# untitled.net
KiCad netlist of a schematic drawn in EAGLE
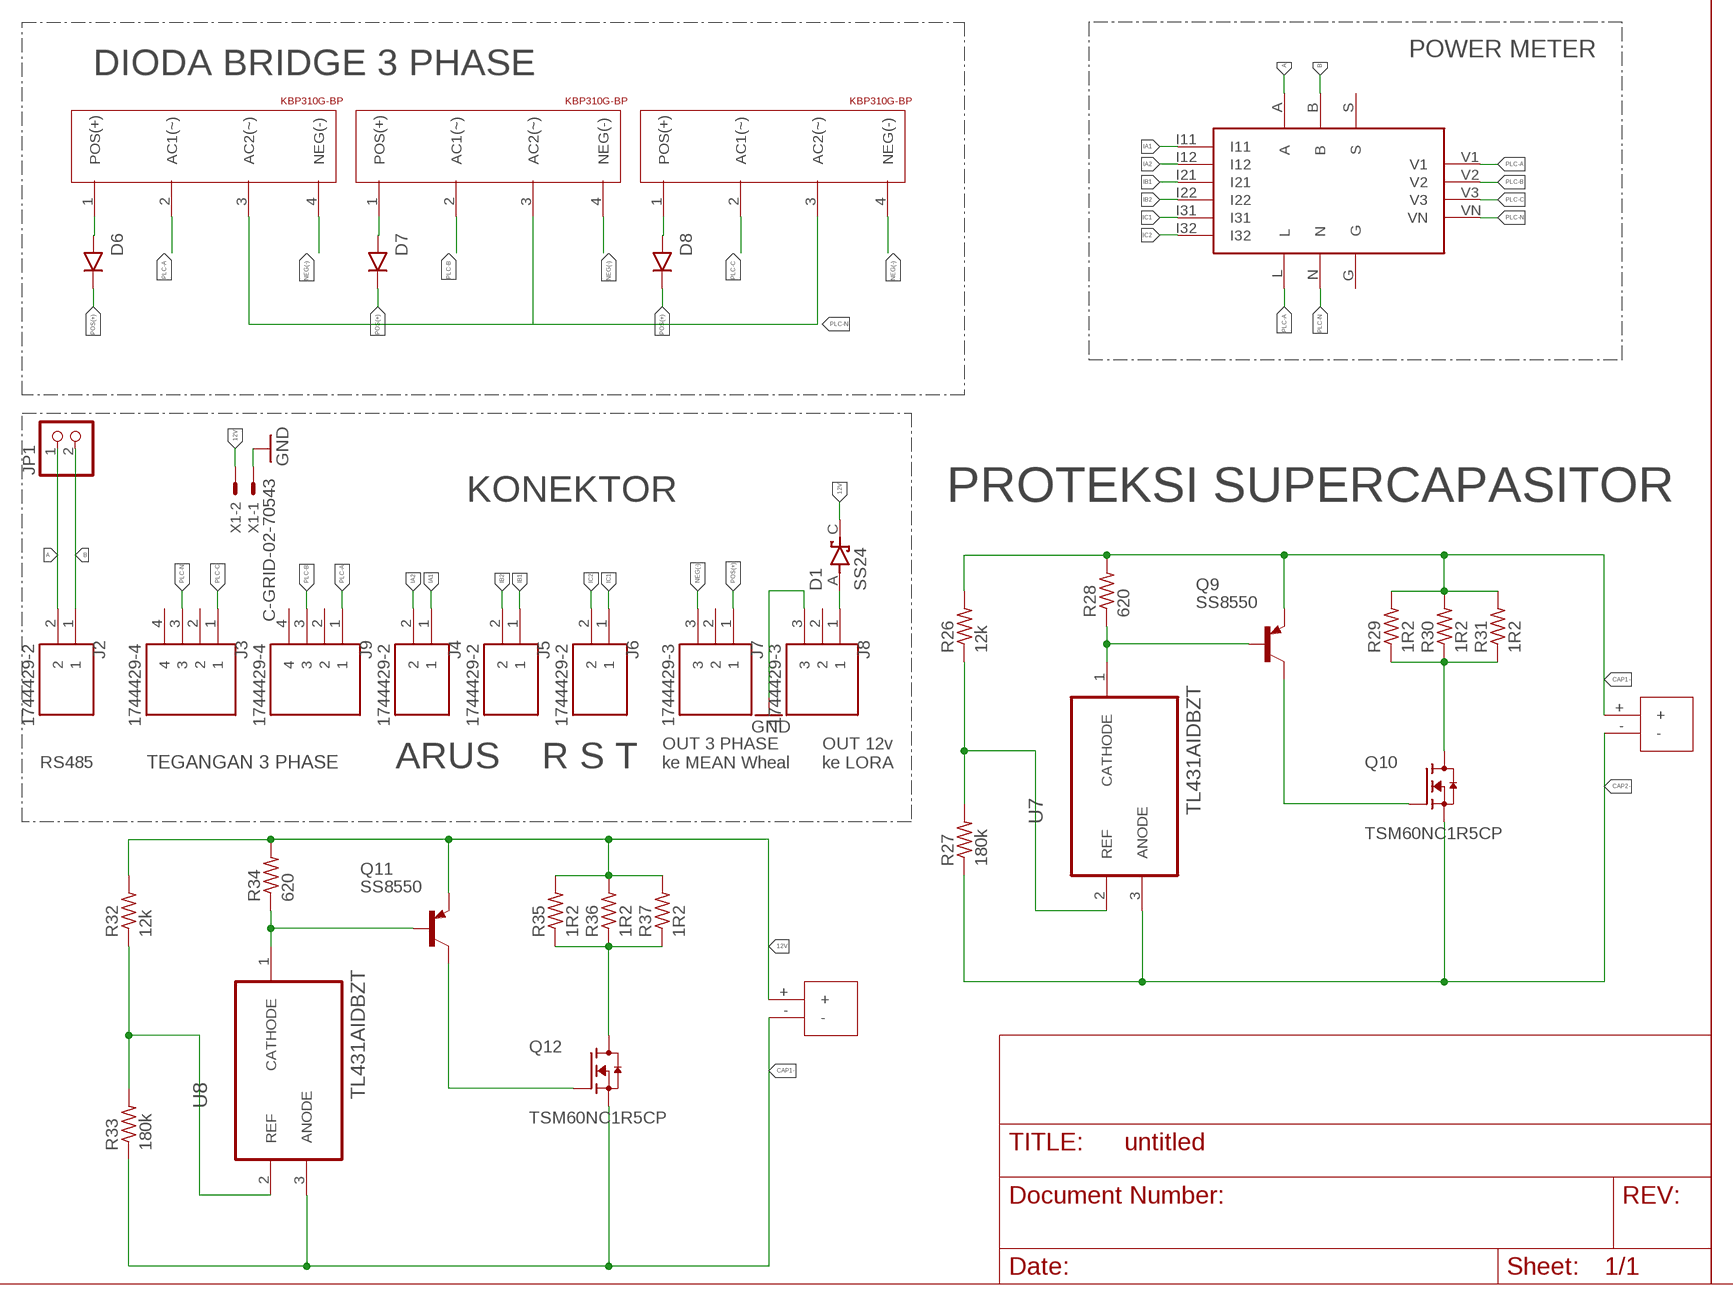
[diagram p0: schematic, sheet 1, part 1 of 2]
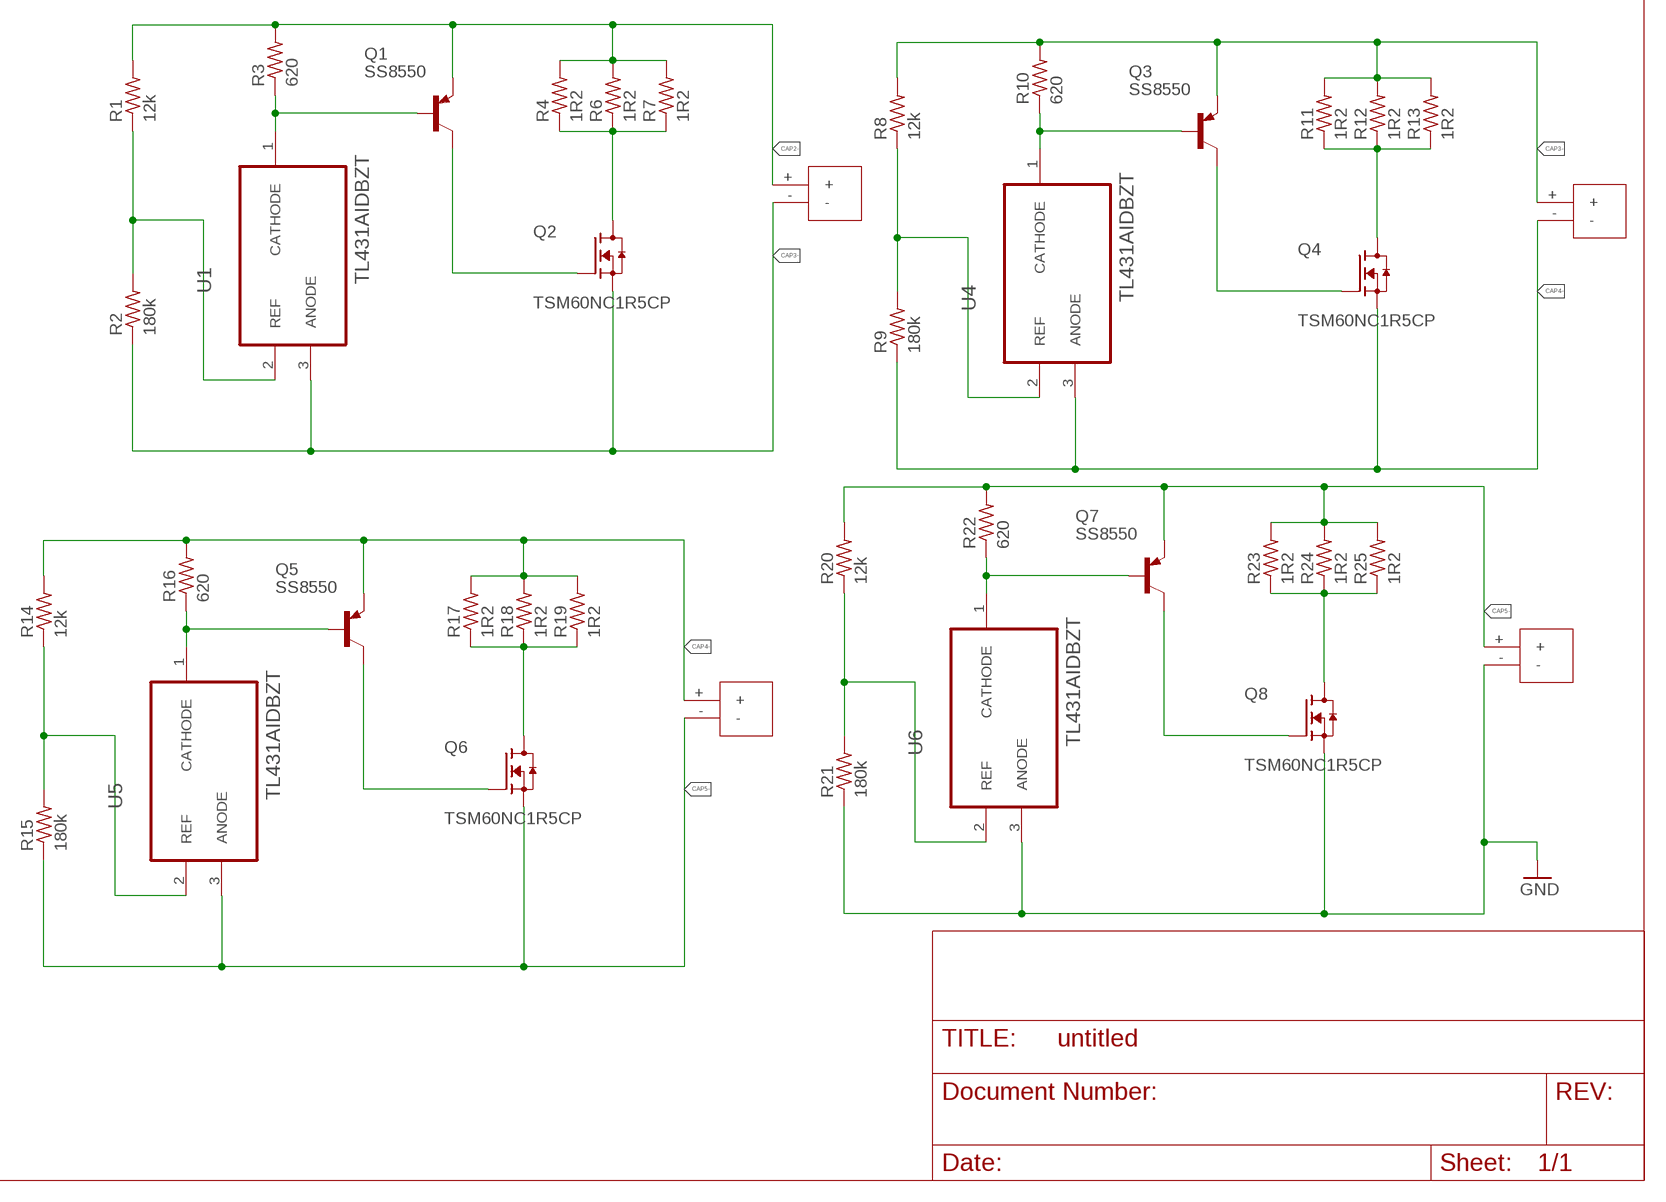
[diagram p1: schematic, sheet 1, part 2 of 2]

(export (version "E")
  (design (tool "Eeschema 10.0.6"))
  (components
    (comp (ref "D1")
      (value "SS24")
      (footprint "eagle-import:DIOM5336X265N")
      (fields (field (name "MF") "ON Semiconductor"))
      (libsource (lib "eagle-import") (part "SS24"))
    )
    (comp (ref "D6")
      (value "1N4001")
      (footprint "eagle-import:DO41-10")
      (fields (field (name "MF") "HVCA"))
      (libsource (lib "eagle-import") (part "1N4001"))
    )
    (comp (ref "D7")
      (value "1N4001")
      (footprint "eagle-import:DO41-10")
      (fields (field (name "MF") "HVCA"))
      (libsource (lib "eagle-import") (part "1N4001"))
    )
    (comp (ref "D8")
      (value "1N4001")
      (footprint "eagle-import:DO41-10")
      (fields (field (name "MF") "HVCA"))
      (libsource (lib "eagle-import") (part "1N4001"))
    )
    (comp (ref "J2")
      (value "1744429-2")
      (footprint "eagle-import:TE_1744429-2")
      (fields (field (name "MF") "TE Connectivity"))
      (libsource (lib "eagle-import") (part "1744429-2"))
    )
    (comp (ref "J3")
      (value "1744429-4")
      (footprint "eagle-import:TE_1744429-4")
      (fields (field (name "MF") "TE Connectivity"))
      (libsource (lib "eagle-import") (part "1744429-4"))
    )
    (comp (ref "J4")
      (value "1744429-2")
      (footprint "eagle-import:TE_1744429-2")
      (fields (field (name "MF") "TE Connectivity"))
      (libsource (lib "eagle-import") (part "1744429-2"))
    )
    (comp (ref "J5")
      (value "1744429-2")
      (footprint "eagle-import:TE_1744429-2")
      (fields (field (name "MF") "TE Connectivity"))
      (libsource (lib "eagle-import") (part "1744429-2"))
    )
    (comp (ref "J6")
      (value "1744429-2")
      (footprint "eagle-import:TE_1744429-2")
      (fields (field (name "MF") "TE Connectivity"))
      (libsource (lib "eagle-import") (part "1744429-2"))
    )
    (comp (ref "J7")
      (value "1744429-3")
      (footprint "eagle-import:TE_1744429-3")
      (fields (field (name "MANUFACTURER") "TE"))
      (libsource (lib "eagle-import") (part "1744429-3"))
    )
    (comp (ref "J8")
      (value "1744429-3")
      (footprint "eagle-import:TE_1744429-3")
      (fields (field (name "MANUFACTURER") "TE"))
      (libsource (lib "eagle-import") (part "1744429-3"))
    )
    (comp (ref "J9")
      (value "1744429-4")
      (footprint "eagle-import:TE_1744429-4")
      (fields (field (name "MF") "TE Connectivity"))
      (libsource (lib "eagle-import") (part "1744429-4"))
    )
    (comp (ref "JP1")
      (value "PINHD-1X2")
      (footprint "eagle-import:1X02")
      (libsource (lib "eagle-import") (part "PINHD-1X2"))
    )
    (comp (ref "POWERMETER1")
      (value "POWERMETER")
      (footprint "eagle-import:POWERMETER")
      (libsource (lib "eagle-import") (part "POWERMETER"))
    )
    (comp (ref "Q1")
      (value "SS8550")
      (footprint "eagle-import:SOT-23_BEC")
      (fields (field (name "MF") "ON Semiconductor / Fairchild"))
      (libsource (lib "eagle-import") (part "SS8550"))
    )
    (comp (ref "Q2")
      (value "TSM60NC1R5CP")
      (footprint "eagle-import:TRANS_TSM60NC1R5CP")
      (fields (field (name "MF") "Taiwan Semiconductor"))
      (libsource (lib "eagle-import") (part "TSM60NC1R5CP"))
    )
    (comp (ref "Q3")
      (value "SS8550")
      (footprint "eagle-import:SOT-23_BEC")
      (fields (field (name "MF") "ON Semiconductor / Fairchild"))
      (libsource (lib "eagle-import") (part "SS8550"))
    )
    (comp (ref "Q4")
      (value "TSM60NC1R5CP")
      (footprint "eagle-import:TRANS_TSM60NC1R5CP")
      (fields (field (name "MF") "Taiwan Semiconductor"))
      (libsource (lib "eagle-import") (part "TSM60NC1R5CP"))
    )
    (comp (ref "Q5")
      (value "SS8550")
      (footprint "eagle-import:SOT-23_BEC")
      (fields (field (name "MF") "ON Semiconductor / Fairchild"))
      (libsource (lib "eagle-import") (part "SS8550"))
    )
    (comp (ref "Q6")
      (value "TSM60NC1R5CP")
      (footprint "eagle-import:TRANS_TSM60NC1R5CP")
      (fields (field (name "MF") "Taiwan Semiconductor"))
      (libsource (lib "eagle-import") (part "TSM60NC1R5CP"))
    )
    (comp (ref "Q7")
      (value "SS8550")
      (footprint "eagle-import:SOT-23_BEC")
      (fields (field (name "MF") "ON Semiconductor / Fairchild"))
      (libsource (lib "eagle-import") (part "SS8550"))
    )
    (comp (ref "Q8")
      (value "TSM60NC1R5CP")
      (footprint "eagle-import:TRANS_TSM60NC1R5CP")
      (fields (field (name "MF") "Taiwan Semiconductor"))
      (libsource (lib "eagle-import") (part "TSM60NC1R5CP"))
    )
    (comp (ref "Q9")
      (value "SS8550")
      (footprint "eagle-import:SOT-23_BEC")
      (fields (field (name "MF") "ON Semiconductor / Fairchild"))
      (libsource (lib "eagle-import") (part "SS8550"))
    )
    (comp (ref "Q10")
      (value "TSM60NC1R5CP")
      (footprint "eagle-import:TRANS_TSM60NC1R5CP")
      (fields (field (name "MF") "Taiwan Semiconductor"))
      (libsource (lib "eagle-import") (part "TSM60NC1R5CP"))
    )
    (comp (ref "Q11")
      (value "SS8550")
      (footprint "eagle-import:SOT-23_BEC")
      (fields (field (name "MF") "ON Semiconductor / Fairchild"))
      (libsource (lib "eagle-import") (part "SS8550"))
    )
    (comp (ref "Q12")
      (value "TSM60NC1R5CP")
      (footprint "eagle-import:TRANS_TSM60NC1R5CP")
      (fields (field (name "MF") "Taiwan Semiconductor"))
      (libsource (lib "eagle-import") (part "TSM60NC1R5CP"))
    )
    (comp (ref "R1")
      (value "12k")
      (footprint "eagle-import:R0805")
      (libsource (lib "eagle-import") (part "R-US_R0805"))
    )
    (comp (ref "R2")
      (value "180k")
      (footprint "eagle-import:R0805")
      (libsource (lib "eagle-import") (part "R-US_R0805"))
    )
    (comp (ref "R3")
      (value "620")
      (footprint "eagle-import:R0805")
      (libsource (lib "eagle-import") (part "R-US_R0805"))
    )
    (comp (ref "R4")
      (value "1R2")
      (footprint "eagle-import:R2512")
      (libsource (lib "eagle-import") (part "rcl_334_R-US_R2512"))
    )
    (comp (ref "R6")
      (value "1R2")
      (footprint "eagle-import:R2512")
      (libsource (lib "eagle-import") (part "rcl_334_R-US_R2512"))
    )
    (comp (ref "R7")
      (value "1R2")
      (footprint "eagle-import:R2512")
      (libsource (lib "eagle-import") (part "rcl_334_R-US_R2512"))
    )
    (comp (ref "R8")
      (value "12k")
      (footprint "eagle-import:R0805")
      (libsource (lib "eagle-import") (part "R-US_R0805"))
    )
    (comp (ref "R9")
      (value "180k")
      (footprint "eagle-import:R0805")
      (libsource (lib "eagle-import") (part "R-US_R0805"))
    )
    (comp (ref "R10")
      (value "620")
      (footprint "eagle-import:R0805")
      (libsource (lib "eagle-import") (part "R-US_R0805"))
    )
    (comp (ref "R11")
      (value "1R2")
      (footprint "eagle-import:R2512")
      (libsource (lib "eagle-import") (part "rcl_334_R-US_R2512"))
    )
    (comp (ref "R12")
      (value "1R2")
      (footprint "eagle-import:R2512")
      (libsource (lib "eagle-import") (part "rcl_334_R-US_R2512"))
    )
    (comp (ref "R13")
      (value "1R2")
      (footprint "eagle-import:R2512")
      (libsource (lib "eagle-import") (part "rcl_334_R-US_R2512"))
    )
    (comp (ref "R14")
      (value "12k")
      (footprint "eagle-import:R0805")
      (libsource (lib "eagle-import") (part "R-US_R0805"))
    )
    (comp (ref "R15")
      (value "180k")
      (footprint "eagle-import:R0805")
      (libsource (lib "eagle-import") (part "R-US_R0805"))
    )
    (comp (ref "R16")
      (value "620")
      (footprint "eagle-import:R0805")
      (libsource (lib "eagle-import") (part "R-US_R0805"))
    )
    (comp (ref "R17")
      (value "1R2")
      (footprint "eagle-import:R2512")
      (libsource (lib "eagle-import") (part "rcl_334_R-US_R2512"))
    )
    (comp (ref "R18")
      (value "1R2")
      (footprint "eagle-import:R2512")
      (libsource (lib "eagle-import") (part "rcl_334_R-US_R2512"))
    )
    (comp (ref "R19")
      (value "1R2")
      (footprint "eagle-import:R2512")
      (libsource (lib "eagle-import") (part "rcl_334_R-US_R2512"))
    )
    (comp (ref "R20")
      (value "12k")
      (footprint "eagle-import:R0805")
      (libsource (lib "eagle-import") (part "R-US_R0805"))
    )
    (comp (ref "R21")
      (value "180k")
      (footprint "eagle-import:R0805")
      (libsource (lib "eagle-import") (part "R-US_R0805"))
    )
    (comp (ref "R22")
      (value "620")
      (footprint "eagle-import:R0805")
      (libsource (lib "eagle-import") (part "R-US_R0805"))
    )
    (comp (ref "R23")
      (value "1R2")
      (footprint "eagle-import:R2512")
      (libsource (lib "eagle-import") (part "rcl_334_R-US_R2512"))
    )
    (comp (ref "R24")
      (value "1R2")
      (footprint "eagle-import:R2512")
      (libsource (lib "eagle-import") (part "rcl_334_R-US_R2512"))
    )
    (comp (ref "R25")
      (value "1R2")
      (footprint "eagle-import:R2512")
      (libsource (lib "eagle-import") (part "rcl_334_R-US_R2512"))
    )
    (comp (ref "R26")
      (value "12k")
      (footprint "eagle-import:R0805")
      (libsource (lib "eagle-import") (part "R-US_R0805"))
    )
    (comp (ref "R27")
      (value "180k")
      (footprint "eagle-import:R0805")
      (libsource (lib "eagle-import") (part "R-US_R0805"))
    )
    (comp (ref "R28")
      (value "620")
      (footprint "eagle-import:R0805")
      (libsource (lib "eagle-import") (part "R-US_R0805"))
    )
    (comp (ref "R29")
      (value "1R2")
      (footprint "eagle-import:R2512")
      (libsource (lib "eagle-import") (part "rcl_334_R-US_R2512"))
    )
    (comp (ref "R30")
      (value "1R2")
      (footprint "eagle-import:R2512")
      (libsource (lib "eagle-import") (part "rcl_334_R-US_R2512"))
    )
    (comp (ref "R31")
      (value "1R2")
      (footprint "eagle-import:R2512")
      (libsource (lib "eagle-import") (part "rcl_334_R-US_R2512"))
    )
    (comp (ref "R32")
      (value "12k")
      (footprint "eagle-import:R0805")
      (libsource (lib "eagle-import") (part "R-US_R0805"))
    )
    (comp (ref "R33")
      (value "180k")
      (footprint "eagle-import:R0805")
      (libsource (lib "eagle-import") (part "R-US_R0805"))
    )
    (comp (ref "R34")
      (value "620")
      (footprint "eagle-import:R0805")
      (libsource (lib "eagle-import") (part "R-US_R0805"))
    )
    (comp (ref "R35")
      (value "1R2")
      (footprint "eagle-import:R2512")
      (libsource (lib "eagle-import") (part "rcl_334_R-US_R2512"))
    )
    (comp (ref "R36")
      (value "1R2")
      (footprint "eagle-import:R2512")
      (libsource (lib "eagle-import") (part "rcl_334_R-US_R2512"))
    )
    (comp (ref "R37")
      (value "1R2")
      (footprint "eagle-import:R2512")
      (libsource (lib "eagle-import") (part "rcl_334_R-US_R2512"))
    )
    (comp (ref "SUPERCAP1")
      (value "2.7/500F")
      (footprint "eagle-import:SUPERCAP")
      (libsource (lib "eagle-import") (part "SUPERCAP"))
    )
    (comp (ref "SUPERCAP2")
      (value "2.7/500F")
      (footprint "eagle-import:SUPERCAP")
      (libsource (lib "eagle-import") (part "SUPERCAP"))
    )
    (comp (ref "SUPERCAP3")
      (value "2.7/500F")
      (footprint "eagle-import:SUPERCAP")
      (libsource (lib "eagle-import") (part "SUPERCAP"))
    )
    (comp (ref "SUPERCAP4")
      (value "2.7/500F")
      (footprint "eagle-import:SUPERCAP")
      (libsource (lib "eagle-import") (part "SUPERCAP"))
    )
    (comp (ref "SUPERCAP5")
      (value "2.7/500F")
      (footprint "eagle-import:SUPERCAP")
      (libsource (lib "eagle-import") (part "SUPERCAP"))
    )
    (comp (ref "SUPERCAP6")
      (value "2.7/500F")
      (footprint "eagle-import:SUPERCAP")
      (libsource (lib "eagle-import") (part "SUPERCAP"))
    )
    (comp (ref "U$1")
      (value "KBP310G-BP")
      (footprint "eagle-import:KBP310G-BP")
      (fields (field (name "MF") "Micro Commercial"))
      (libsource (lib "eagle-import") (part "KBP310G-BP"))
    )
    (comp (ref "U$2")
      (value "KBP310G-BP")
      (footprint "eagle-import:KBP310G-BP")
      (fields (field (name "MF") "Micro Commercial"))
      (libsource (lib "eagle-import") (part "KBP310G-BP"))
    )
    (comp (ref "U$3")
      (value "KBP310G-BP")
      (footprint "eagle-import:KBP310G-BP")
      (fields (field (name "MF") "Micro Commercial"))
      (libsource (lib "eagle-import") (part "KBP310G-BP"))
    )
    (comp (ref "U1")
      (value "TL431AIDBZT")
      (footprint "eagle-import:SOT95P237X112-3N")
      (fields (field (name "MF") "Texas Instruments"))
      (libsource (lib "eagle-import") (part "TL431AIDBZT"))
    )
    (comp (ref "U4")
      (value "TL431AIDBZT")
      (footprint "eagle-import:SOT95P237X112-3N")
      (fields (field (name "MF") "Texas Instruments"))
      (libsource (lib "eagle-import") (part "TL431AIDBZT"))
    )
    (comp (ref "U5")
      (value "TL431AIDBZT")
      (footprint "eagle-import:SOT95P237X112-3N")
      (fields (field (name "MF") "Texas Instruments"))
      (libsource (lib "eagle-import") (part "TL431AIDBZT"))
    )
    (comp (ref "U6")
      (value "TL431AIDBZT")
      (footprint "eagle-import:SOT95P237X112-3N")
      (fields (field (name "MF") "Texas Instruments"))
      (libsource (lib "eagle-import") (part "TL431AIDBZT"))
    )
    (comp (ref "U7")
      (value "TL431AIDBZT")
      (footprint "eagle-import:SOT95P237X112-3N")
      (fields (field (name "MF") "Texas Instruments"))
      (libsource (lib "eagle-import") (part "TL431AIDBZT"))
    )
    (comp (ref "U8")
      (value "TL431AIDBZT")
      (footprint "eagle-import:SOT95P237X112-3N")
      (fields (field (name "MF") "Texas Instruments"))
      (libsource (lib "eagle-import") (part "TL431AIDBZT"))
    )
    (comp (ref "X1")
      (value "C-GRID-02-70543")
      (footprint "eagle-import:70543-02")
      (fields (field (name "MF") "MOLEX"))
      (libsource (lib "eagle-import") (part "C-GRID-02-70543"))
    )
  )
  (nets
    (net (code "1") (name "12V") (class "Default")
      (node (ref "D1") (pin "C") (pinfunction "K_C") (pintype "passive"))
      (node (ref "Q11") (pin "E") (pinfunction "E_E") (pintype "passive"))
      (node (ref "R32") (pin "2") (pinfunction "2_2") (pintype "passive"))
      (node (ref "R34") (pin "2") (pinfunction "2_2") (pintype "passive"))
      (node (ref "R35") (pin "2") (pinfunction "2_2") (pintype "passive"))
      (node (ref "R36") (pin "2") (pinfunction "2_2") (pintype "passive"))
      (node (ref "R37") (pin "2") (pinfunction "2_2") (pintype "passive"))
      (node (ref "SUPERCAP6") (pin "+") (pinfunction "+_+") (pintype "bidirectional"))
      (node (ref "X1") (pin "2") (pinfunction "S_2") (pintype "passive"))
    )
    (net (code "2") (name "A") (class "Default")
      (node (ref "J2") (pin "2") (pinfunction "2_2") (pintype "passive"))
      (node (ref "JP1") (pin "1") (pinfunction "1_1") (pintype "passive"))
      (node (ref "POWERMETER1") (pin "A") (pinfunction "A_A") (pintype "bidirectional"))
    )
    (net (code "3") (name "B") (class "Default")
      (node (ref "J2") (pin "1") (pinfunction "1_1") (pintype "passive"))
      (node (ref "JP1") (pin "2") (pinfunction "2_2") (pintype "passive"))
      (node (ref "POWERMETER1") (pin "B") (pinfunction "B_B") (pintype "bidirectional"))
    )
    (net (code "4") (name "CAP1-") (class "Default")
      (node (ref "Q12") (pin "3") (pinfunction "S_3") (pintype "passive"))
      (node (ref "Q9") (pin "E") (pinfunction "E_E") (pintype "passive"))
      (node (ref "R26") (pin "2") (pinfunction "2_2") (pintype "passive"))
      (node (ref "R28") (pin "2") (pinfunction "2_2") (pintype "passive"))
      (node (ref "R29") (pin "2") (pinfunction "2_2") (pintype "passive"))
      (node (ref "R30") (pin "2") (pinfunction "2_2") (pintype "passive"))
      (node (ref "R31") (pin "2") (pinfunction "2_2") (pintype "passive"))
      (node (ref "R33") (pin "1") (pinfunction "1_1") (pintype "passive"))
      (node (ref "SUPERCAP5") (pin "+") (pinfunction "+_+") (pintype "bidirectional"))
      (node (ref "SUPERCAP6") (pin "-") (pinfunction "-_-") (pintype "bidirectional"))
      (node (ref "U8") (pin "3") (pinfunction "ANODE_3") (pintype "passive"))
    )
    (net (code "5") (name "CAP2-") (class "Default")
      (node (ref "Q1") (pin "E") (pinfunction "E_E") (pintype "passive"))
      (node (ref "Q10") (pin "3") (pinfunction "S_3") (pintype "passive"))
      (node (ref "R1") (pin "2") (pinfunction "2_2") (pintype "passive"))
      (node (ref "R27") (pin "1") (pinfunction "1_1") (pintype "passive"))
      (node (ref "R3") (pin "2") (pinfunction "2_2") (pintype "passive"))
      (node (ref "R4") (pin "2") (pinfunction "2_2") (pintype "passive"))
      (node (ref "R6") (pin "2") (pinfunction "2_2") (pintype "passive"))
      (node (ref "R7") (pin "2") (pinfunction "2_2") (pintype "passive"))
      (node (ref "SUPERCAP1") (pin "+") (pinfunction "+_+") (pintype "bidirectional"))
      (node (ref "SUPERCAP5") (pin "-") (pinfunction "-_-") (pintype "bidirectional"))
      (node (ref "U7") (pin "3") (pinfunction "ANODE_3") (pintype "passive"))
    )
    (net (code "6") (name "CAP3-") (class "Default")
      (node (ref "Q2") (pin "3") (pinfunction "S_3") (pintype "passive"))
      (node (ref "Q3") (pin "E") (pinfunction "E_E") (pintype "passive"))
      (node (ref "R10") (pin "2") (pinfunction "2_2") (pintype "passive"))
      (node (ref "R11") (pin "2") (pinfunction "2_2") (pintype "passive"))
      (node (ref "R12") (pin "2") (pinfunction "2_2") (pintype "passive"))
      (node (ref "R13") (pin "2") (pinfunction "2_2") (pintype "passive"))
      (node (ref "R2") (pin "1") (pinfunction "1_1") (pintype "passive"))
      (node (ref "R8") (pin "2") (pinfunction "2_2") (pintype "passive"))
      (node (ref "SUPERCAP1") (pin "-") (pinfunction "-_-") (pintype "bidirectional"))
      (node (ref "SUPERCAP2") (pin "+") (pinfunction "+_+") (pintype "bidirectional"))
      (node (ref "U1") (pin "3") (pinfunction "ANODE_3") (pintype "passive"))
    )
    (net (code "7") (name "CAP4-") (class "Default")
      (node (ref "Q4") (pin "3") (pinfunction "S_3") (pintype "passive"))
      (node (ref "Q5") (pin "E") (pinfunction "E_E") (pintype "passive"))
      (node (ref "R14") (pin "2") (pinfunction "2_2") (pintype "passive"))
      (node (ref "R16") (pin "2") (pinfunction "2_2") (pintype "passive"))
      (node (ref "R17") (pin "2") (pinfunction "2_2") (pintype "passive"))
      (node (ref "R18") (pin "2") (pinfunction "2_2") (pintype "passive"))
      (node (ref "R19") (pin "2") (pinfunction "2_2") (pintype "passive"))
      (node (ref "R9") (pin "1") (pinfunction "1_1") (pintype "passive"))
      (node (ref "SUPERCAP2") (pin "-") (pinfunction "-_-") (pintype "bidirectional"))
      (node (ref "SUPERCAP3") (pin "+") (pinfunction "+_+") (pintype "bidirectional"))
      (node (ref "U4") (pin "3") (pinfunction "ANODE_3") (pintype "passive"))
    )
    (net (code "8") (name "CAP5-") (class "Default")
      (node (ref "Q6") (pin "3") (pinfunction "S_3") (pintype "passive"))
      (node (ref "Q7") (pin "E") (pinfunction "E_E") (pintype "passive"))
      (node (ref "R15") (pin "1") (pinfunction "1_1") (pintype "passive"))
      (node (ref "R20") (pin "2") (pinfunction "2_2") (pintype "passive"))
      (node (ref "R22") (pin "2") (pinfunction "2_2") (pintype "passive"))
      (node (ref "R23") (pin "2") (pinfunction "2_2") (pintype "passive"))
      (node (ref "R24") (pin "2") (pinfunction "2_2") (pintype "passive"))
      (node (ref "R25") (pin "2") (pinfunction "2_2") (pintype "passive"))
      (node (ref "SUPERCAP3") (pin "-") (pinfunction "-_-") (pintype "bidirectional"))
      (node (ref "SUPERCAP4") (pin "+") (pinfunction "+_+") (pintype "bidirectional"))
      (node (ref "U5") (pin "3") (pinfunction "ANODE_3") (pintype "passive"))
    )
    (net (code "9") (name "GND") (class "Default")
      (node (ref "J8") (pin "3") (pinfunction "3_3") (pintype "passive"))
      (node (ref "Q8") (pin "3") (pinfunction "S_3") (pintype "passive"))
      (node (ref "R21") (pin "1") (pinfunction "1_1") (pintype "passive"))
      (node (ref "SUPERCAP4") (pin "-") (pinfunction "-_-") (pintype "bidirectional"))
      (node (ref "U6") (pin "3") (pinfunction "ANODE_3") (pintype "passive"))
      (node (ref "X1") (pin "1") (pinfunction "S_1") (pintype "passive"))
    )
    (net (code "10") (name "IA1") (class "Default")
      (node (ref "J4") (pin "1") (pinfunction "1_1") (pintype "passive"))
      (node (ref "POWERMETER1") (pin "I11") (pinfunction "I11_I11") (pintype "bidirectional"))
    )
    (net (code "11") (name "IA2") (class "Default")
      (node (ref "J4") (pin "2") (pinfunction "2_2") (pintype "passive"))
      (node (ref "POWERMETER1") (pin "I12") (pinfunction "I12_I12") (pintype "bidirectional"))
    )
    (net (code "12") (name "IB1") (class "Default")
      (node (ref "J5") (pin "1") (pinfunction "1_1") (pintype "passive"))
      (node (ref "POWERMETER1") (pin "I21") (pinfunction "I21_I21") (pintype "bidirectional"))
    )
    (net (code "13") (name "IB2") (class "Default")
      (node (ref "J5") (pin "2") (pinfunction "2_2") (pintype "passive"))
      (node (ref "POWERMETER1") (pin "I22") (pinfunction "I22_I22") (pintype "bidirectional"))
    )
    (net (code "14") (name "IC1") (class "Default")
      (node (ref "J6") (pin "1") (pinfunction "1_1") (pintype "passive"))
      (node (ref "POWERMETER1") (pin "I31") (pinfunction "I31_I31") (pintype "bidirectional"))
    )
    (net (code "15") (name "IC2") (class "Default")
      (node (ref "J6") (pin "2") (pinfunction "2_2") (pintype "passive"))
      (node (ref "POWERMETER1") (pin "I32") (pinfunction "I32_I32") (pintype "bidirectional"))
    )
    (net (code "16") (name "NEG(-)") (class "Default")
      (node (ref "J7") (pin "3") (pinfunction "3_3") (pintype "passive"))
      (node (ref "U$1") (pin "4") (pinfunction "NEG(-)_4") (pintype "bidirectional"))
      (node (ref "U$2") (pin "4") (pinfunction "NEG(-)_4") (pintype "bidirectional"))
      (node (ref "U$3") (pin "4") (pinfunction "NEG(-)_4") (pintype "bidirectional"))
    )
    (net (code "17") (name "Net-(D1-PadA)") (class "Default")
      (node (ref "D1") (pin "A") (pinfunction "A_A") (pintype "passive"))
      (node (ref "J8") (pin "1") (pinfunction "1_1") (pintype "passive"))
    )
    (net (code "18") (name "Net-(D6-ANODE)") (class "Default")
      (node (ref "D6") (pin "A") (pinfunction "ANODE_A") (pintype "passive"))
      (node (ref "U$1") (pin "1") (pinfunction "POS(+)_1") (pintype "bidirectional"))
    )
    (net (code "19") (name "Net-(D7-ANODE)") (class "Default")
      (node (ref "D7") (pin "A") (pinfunction "ANODE_A") (pintype "passive"))
      (node (ref "U$2") (pin "1") (pinfunction "POS(+)_1") (pintype "bidirectional"))
    )
    (net (code "20") (name "Net-(D8-ANODE)") (class "Default")
      (node (ref "D8") (pin "A") (pinfunction "ANODE_A") (pintype "passive"))
      (node (ref "U$3") (pin "1") (pinfunction "POS(+)_1") (pintype "bidirectional"))
    )
    (net (code "21") (name "Net-(Q2-D)") (class "Default")
      (node (ref "Q2") (pin "2") (pinfunction "D_2") (pintype "passive"))
      (node (ref "R4") (pin "1") (pinfunction "1_1") (pintype "passive"))
      (node (ref "R6") (pin "1") (pinfunction "1_1") (pintype "passive"))
      (node (ref "R7") (pin "1") (pinfunction "1_1") (pintype "passive"))
    )
    (net (code "22") (name "Net-(Q2-G)") (class "Default")
      (node (ref "Q1") (pin "C") (pinfunction "C_C") (pintype "passive"))
      (node (ref "Q2") (pin "1") (pinfunction "G_1") (pintype "passive"))
    )
    (net (code "23") (name "Net-(Q4-D)") (class "Default")
      (node (ref "Q4") (pin "2") (pinfunction "D_2") (pintype "passive"))
      (node (ref "R11") (pin "1") (pinfunction "1_1") (pintype "passive"))
      (node (ref "R12") (pin "1") (pinfunction "1_1") (pintype "passive"))
      (node (ref "R13") (pin "1") (pinfunction "1_1") (pintype "passive"))
    )
    (net (code "24") (name "Net-(Q4-G)") (class "Default")
      (node (ref "Q3") (pin "C") (pinfunction "C_C") (pintype "passive"))
      (node (ref "Q4") (pin "1") (pinfunction "G_1") (pintype "passive"))
    )
    (net (code "25") (name "Net-(Q6-D)") (class "Default")
      (node (ref "Q6") (pin "2") (pinfunction "D_2") (pintype "passive"))
      (node (ref "R17") (pin "1") (pinfunction "1_1") (pintype "passive"))
      (node (ref "R18") (pin "1") (pinfunction "1_1") (pintype "passive"))
      (node (ref "R19") (pin "1") (pinfunction "1_1") (pintype "passive"))
    )
    (net (code "26") (name "Net-(Q6-G)") (class "Default")
      (node (ref "Q5") (pin "C") (pinfunction "C_C") (pintype "passive"))
      (node (ref "Q6") (pin "1") (pinfunction "G_1") (pintype "passive"))
    )
    (net (code "27") (name "Net-(Q8-D)") (class "Default")
      (node (ref "Q8") (pin "2") (pinfunction "D_2") (pintype "passive"))
      (node (ref "R23") (pin "1") (pinfunction "1_1") (pintype "passive"))
      (node (ref "R24") (pin "1") (pinfunction "1_1") (pintype "passive"))
      (node (ref "R25") (pin "1") (pinfunction "1_1") (pintype "passive"))
    )
    (net (code "28") (name "Net-(Q8-G)") (class "Default")
      (node (ref "Q7") (pin "C") (pinfunction "C_C") (pintype "passive"))
      (node (ref "Q8") (pin "1") (pinfunction "G_1") (pintype "passive"))
    )
    (net (code "29") (name "Net-(Q10-D)") (class "Default")
      (node (ref "Q10") (pin "2") (pinfunction "D_2") (pintype "passive"))
      (node (ref "R29") (pin "1") (pinfunction "1_1") (pintype "passive"))
      (node (ref "R30") (pin "1") (pinfunction "1_1") (pintype "passive"))
      (node (ref "R31") (pin "1") (pinfunction "1_1") (pintype "passive"))
    )
    (net (code "30") (name "Net-(Q10-G)") (class "Default")
      (node (ref "Q10") (pin "1") (pinfunction "G_1") (pintype "passive"))
      (node (ref "Q9") (pin "C") (pinfunction "C_C") (pintype "passive"))
    )
    (net (code "31") (name "Net-(Q12-D)") (class "Default")
      (node (ref "Q12") (pin "2") (pinfunction "D_2") (pintype "passive"))
      (node (ref "R35") (pin "1") (pinfunction "1_1") (pintype "passive"))
      (node (ref "R36") (pin "1") (pinfunction "1_1") (pintype "passive"))
      (node (ref "R37") (pin "1") (pinfunction "1_1") (pintype "passive"))
    )
    (net (code "32") (name "Net-(Q12-G)") (class "Default")
      (node (ref "Q11") (pin "C") (pinfunction "C_C") (pintype "passive"))
      (node (ref "Q12") (pin "1") (pinfunction "G_1") (pintype "passive"))
    )
    (net (code "33") (name "Net-(U1-CATHODE)") (class "Default")
      (node (ref "Q1") (pin "B") (pinfunction "B_B") (pintype "passive"))
      (node (ref "R3") (pin "1") (pinfunction "1_1") (pintype "passive"))
      (node (ref "U1") (pin "1") (pinfunction "CATHODE_1") (pintype "passive"))
    )
    (net (code "34") (name "Net-(U1-REF)") (class "Default")
      (node (ref "R1") (pin "1") (pinfunction "1_1") (pintype "passive"))
      (node (ref "R2") (pin "2") (pinfunction "2_2") (pintype "passive"))
      (node (ref "U1") (pin "2") (pinfunction "REF_2") (pintype "power_in"))
    )
    (net (code "35") (name "Net-(U4-CATHODE)") (class "Default")
      (node (ref "Q3") (pin "B") (pinfunction "B_B") (pintype "passive"))
      (node (ref "R10") (pin "1") (pinfunction "1_1") (pintype "passive"))
      (node (ref "U4") (pin "1") (pinfunction "CATHODE_1") (pintype "passive"))
    )
    (net (code "36") (name "Net-(U4-REF)") (class "Default")
      (node (ref "R8") (pin "1") (pinfunction "1_1") (pintype "passive"))
      (node (ref "R9") (pin "2") (pinfunction "2_2") (pintype "passive"))
      (node (ref "U4") (pin "2") (pinfunction "REF_2") (pintype "power_in"))
    )
    (net (code "37") (name "Net-(U5-CATHODE)") (class "Default")
      (node (ref "Q5") (pin "B") (pinfunction "B_B") (pintype "passive"))
      (node (ref "R16") (pin "1") (pinfunction "1_1") (pintype "passive"))
      (node (ref "U5") (pin "1") (pinfunction "CATHODE_1") (pintype "passive"))
    )
    (net (code "38") (name "Net-(U5-REF)") (class "Default")
      (node (ref "R14") (pin "1") (pinfunction "1_1") (pintype "passive"))
      (node (ref "R15") (pin "2") (pinfunction "2_2") (pintype "passive"))
      (node (ref "U5") (pin "2") (pinfunction "REF_2") (pintype "power_in"))
    )
    (net (code "39") (name "Net-(U6-CATHODE)") (class "Default")
      (node (ref "Q7") (pin "B") (pinfunction "B_B") (pintype "passive"))
      (node (ref "R22") (pin "1") (pinfunction "1_1") (pintype "passive"))
      (node (ref "U6") (pin "1") (pinfunction "CATHODE_1") (pintype "passive"))
    )
    (net (code "40") (name "Net-(U6-REF)") (class "Default")
      (node (ref "R20") (pin "1") (pinfunction "1_1") (pintype "passive"))
      (node (ref "R21") (pin "2") (pinfunction "2_2") (pintype "passive"))
      (node (ref "U6") (pin "2") (pinfunction "REF_2") (pintype "power_in"))
    )
    (net (code "41") (name "Net-(U7-CATHODE)") (class "Default")
      (node (ref "Q9") (pin "B") (pinfunction "B_B") (pintype "passive"))
      (node (ref "R28") (pin "1") (pinfunction "1_1") (pintype "passive"))
      (node (ref "U7") (pin "1") (pinfunction "CATHODE_1") (pintype "passive"))
    )
    (net (code "42") (name "Net-(U7-REF)") (class "Default")
      (node (ref "R26") (pin "1") (pinfunction "1_1") (pintype "passive"))
      (node (ref "R27") (pin "2") (pinfunction "2_2") (pintype "passive"))
      (node (ref "U7") (pin "2") (pinfunction "REF_2") (pintype "power_in"))
    )
    (net (code "43") (name "Net-(U8-CATHODE)") (class "Default")
      (node (ref "Q11") (pin "B") (pinfunction "B_B") (pintype "passive"))
      (node (ref "R34") (pin "1") (pinfunction "1_1") (pintype "passive"))
      (node (ref "U8") (pin "1") (pinfunction "CATHODE_1") (pintype "passive"))
    )
    (net (code "44") (name "Net-(U8-REF)") (class "Default")
      (node (ref "R32") (pin "1") (pinfunction "1_1") (pintype "passive"))
      (node (ref "R33") (pin "2") (pinfunction "2_2") (pintype "passive"))
      (node (ref "U8") (pin "2") (pinfunction "REF_2") (pintype "power_in"))
    )
    (net (code "45") (name "PLC-A") (class "Default")
      (node (ref "J9") (pin "1") (pinfunction "1_1") (pintype "passive"))
      (node (ref "POWERMETER1") (pin "L") (pinfunction "L_L") (pintype "bidirectional"))
      (node (ref "POWERMETER1") (pin "V1") (pinfunction "V1_V1") (pintype "bidirectional"))
      (node (ref "U$1") (pin "2") (pinfunction "AC1(~{})_2") (pintype "bidirectional"))
    )
    (net (code "46") (name "PLC-B") (class "Default")
      (node (ref "J9") (pin "3") (pinfunction "3_3") (pintype "passive"))
      (node (ref "POWERMETER1") (pin "V2") (pinfunction "V2_V2") (pintype "bidirectional"))
      (node (ref "U$2") (pin "2") (pinfunction "AC1(~{})_2") (pintype "bidirectional"))
    )
    (net (code "47") (name "PLC-C") (class "Default")
      (node (ref "J3") (pin "1") (pinfunction "1_1") (pintype "passive"))
      (node (ref "POWERMETER1") (pin "V3") (pinfunction "V3_V3") (pintype "bidirectional"))
      (node (ref "U$3") (pin "2") (pinfunction "AC1(~{})_2") (pintype "bidirectional"))
    )
    (net (code "48") (name "PLC-N") (class "Default")
      (node (ref "J3") (pin "3") (pinfunction "3_3") (pintype "passive"))
      (node (ref "POWERMETER1") (pin "N") (pinfunction "N_N") (pintype "bidirectional"))
      (node (ref "POWERMETER1") (pin "VN") (pinfunction "VN_VN") (pintype "bidirectional"))
      (node (ref "U$1") (pin "3") (pinfunction "AC2(~{})_3") (pintype "bidirectional"))
      (node (ref "U$2") (pin "3") (pinfunction "AC2(~{})_3") (pintype "bidirectional"))
      (node (ref "U$3") (pin "3") (pinfunction "AC2(~{})_3") (pintype "bidirectional"))
    )
    (net (code "49") (name "POS(+)") (class "Default")
      (node (ref "D6") (pin "C") (pinfunction "CATHODE_C") (pintype "passive"))
      (node (ref "D7") (pin "C") (pinfunction "CATHODE_C") (pintype "passive"))
      (node (ref "D8") (pin "C") (pinfunction "CATHODE_C") (pintype "passive"))
      (node (ref "J7") (pin "1") (pinfunction "1_1") (pintype "passive"))
    )
    (net (code "50") (name "unconnected-(J3-Pad2)") (class "Default")
      (node (ref "J3") (pin "2") (pinfunction "2_2") (pintype "passive"))
    )
    (net (code "51") (name "unconnected-(J3-Pad4)") (class "Default")
      (node (ref "J3") (pin "4") (pinfunction "4_4") (pintype "passive"))
    )
    (net (code "52") (name "unconnected-(J7-Pad2)") (class "Default")
      (node (ref "J7") (pin "2") (pinfunction "2_2") (pintype "passive"))
    )
    (net (code "53") (name "unconnected-(J8-Pad2)") (class "Default")
      (node (ref "J8") (pin "2") (pinfunction "2_2") (pintype "passive"))
    )
    (net (code "54") (name "unconnected-(J9-Pad2)") (class "Default")
      (node (ref "J9") (pin "2") (pinfunction "2_2") (pintype "passive"))
    )
    (net (code "55") (name "unconnected-(J9-Pad4)") (class "Default")
      (node (ref "J9") (pin "4") (pinfunction "4_4") (pintype "passive"))
    )
    (net (code "56") (name "unconnected-(POWERMETER1-PadG)") (class "Default")
      (node (ref "POWERMETER1") (pin "G") (pinfunction "G_G") (pintype "bidirectional"))
    )
    (net (code "57") (name "unconnected-(POWERMETER1-PadS)") (class "Default")
      (node (ref "POWERMETER1") (pin "S") (pinfunction "S_S") (pintype "bidirectional"))
    )
  )
)
